# Power.net
KiCad netlist of a schematic drawn in Altium Designer
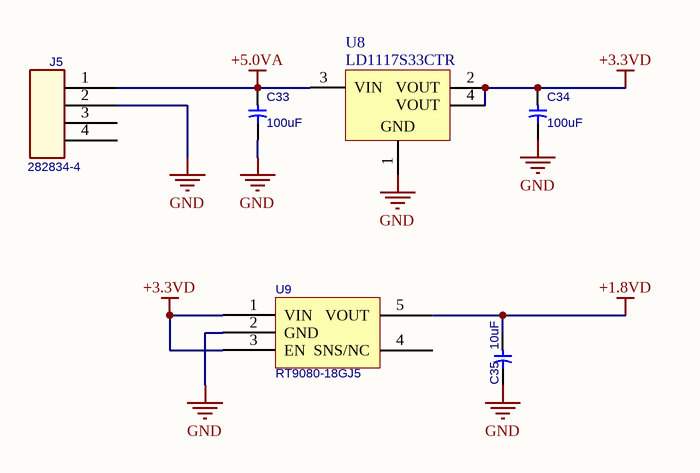
[diagram p0: Power.SchDoc]

(export (version "E")
  (design (tool "Eeschema 10.0.6"))
  (components
    (comp (ref "C33") (value "100uF") (footprint "C_1210D") (libsource (lib "WiFi_3200") (part "C_1210")))
    (comp (ref "C34") (value "100uF") (footprint "C_1210D") (libsource (lib "WiFi_3200") (part "C_1210")))
    (comp (ref "C35") (value "10uF") (footprint "C_0603A") (libsource (lib "WiFi_3200") (part "C_0603")))
    (comp (ref "J5")
      (value "282834-4")
      (footprint "HEADER_2.54_SCREW_4PIN")
      (fields (field (name "MANUFACTURER") "TE CONNECTIVITY / BUCHANAN"))
      (libsource (lib "WiFi_3200") (part "TERM_LIST_4"))
    )
    (comp (ref "U8")
      (value "LD1117S33CTR")
      (footprint "SOT-223_L")
      (description "Fixed Low Drop Positive Voltage Regulator, 3.3V, 4-Pin SOT-223, Tape and Reel")
      (libsource (lib "Altium Content Vault") (part "CMP-0244-00307-1"))
    )
    (comp (ref "U9")
      (value "RT9080-18GJ5")
      (footprint "SOT95P275X100-5N")
      (description "LDO 1.8V, 600mA")
      (fields (field (name "MANUFACTURER") "Richtek USA Inc."))
      (libsource (lib "WiFi_3200") (part "RT9080-18GJ5"))
    )
  )
  (nets
    (net (code "1") (name "+1.8VD") (class "Default")
      (node (ref "C35") (pin "1") (pinfunction "1_1") (pintype "passive"))
      (node (ref "U9") (pin "5") (pinfunction "VOUT_5") (pintype "passive"))
    )
    (net (code "2") (name "+3.3VD") (class "Default")
      (node (ref "C34") (pin "1") (pinfunction "1_1") (pintype "passive"))
      (node (ref "U8") (pin "2") (pinfunction "VOUT_2") (pintype "power_in"))
      (node (ref "U8") (pin "4") (pinfunction "VOUT_4") (pintype "power_in"))
      (node (ref "U9") (pin "1") (pinfunction "VIN_1") (pintype "passive"))
      (node (ref "U9") (pin "3") (pinfunction "EN_3") (pintype "passive"))
    )
    (net (code "3") (name "+5.0VA") (class "Default")
      (node (ref "C33") (pin "1") (pinfunction "1_1") (pintype "passive"))
      (node (ref "J5") (pin "1") (pinfunction "1_1") (pintype "passive"))
      (node (ref "U8") (pin "3") (pinfunction "VIN_3") (pintype "power_in"))
    )
    (net (code "4") (name "GND") (class "Default")
      (node (ref "C33") (pin "2") (pinfunction "2_2") (pintype "passive"))
      (node (ref "C34") (pin "2") (pinfunction "2_2") (pintype "passive"))
      (node (ref "C35") (pin "2") (pinfunction "2_2") (pintype "passive"))
      (node (ref "J5") (pin "2") (pinfunction "2_2") (pintype "passive"))
      (node (ref "U8") (pin "1") (pinfunction "GND_1") (pintype "power_in"))
      (node (ref "U9") (pin "2") (pinfunction "GND_2") (pintype "passive"))
    )
    (net (code "5") (name "unconnected-(J5-Pad3)") (class "Default")
      (node (ref "J5") (pin "3") (pinfunction "3_3") (pintype "passive"))
    )
    (net (code "6") (name "unconnected-(J5-Pad4)") (class "Default")
      (node (ref "J5") (pin "4") (pinfunction "4_4") (pintype "passive"))
    )
    (net (code "7") (name "unconnected-(U9-SNS{slash}NC-Pad4)") (class "Default")
      (node (ref "U9") (pin "4") (pinfunction "SNS/NC_4") (pintype "passive"))
    )
  )
)
